# rtk1010_test.net
KiCad netlist of a schematic drawn in EAGLE
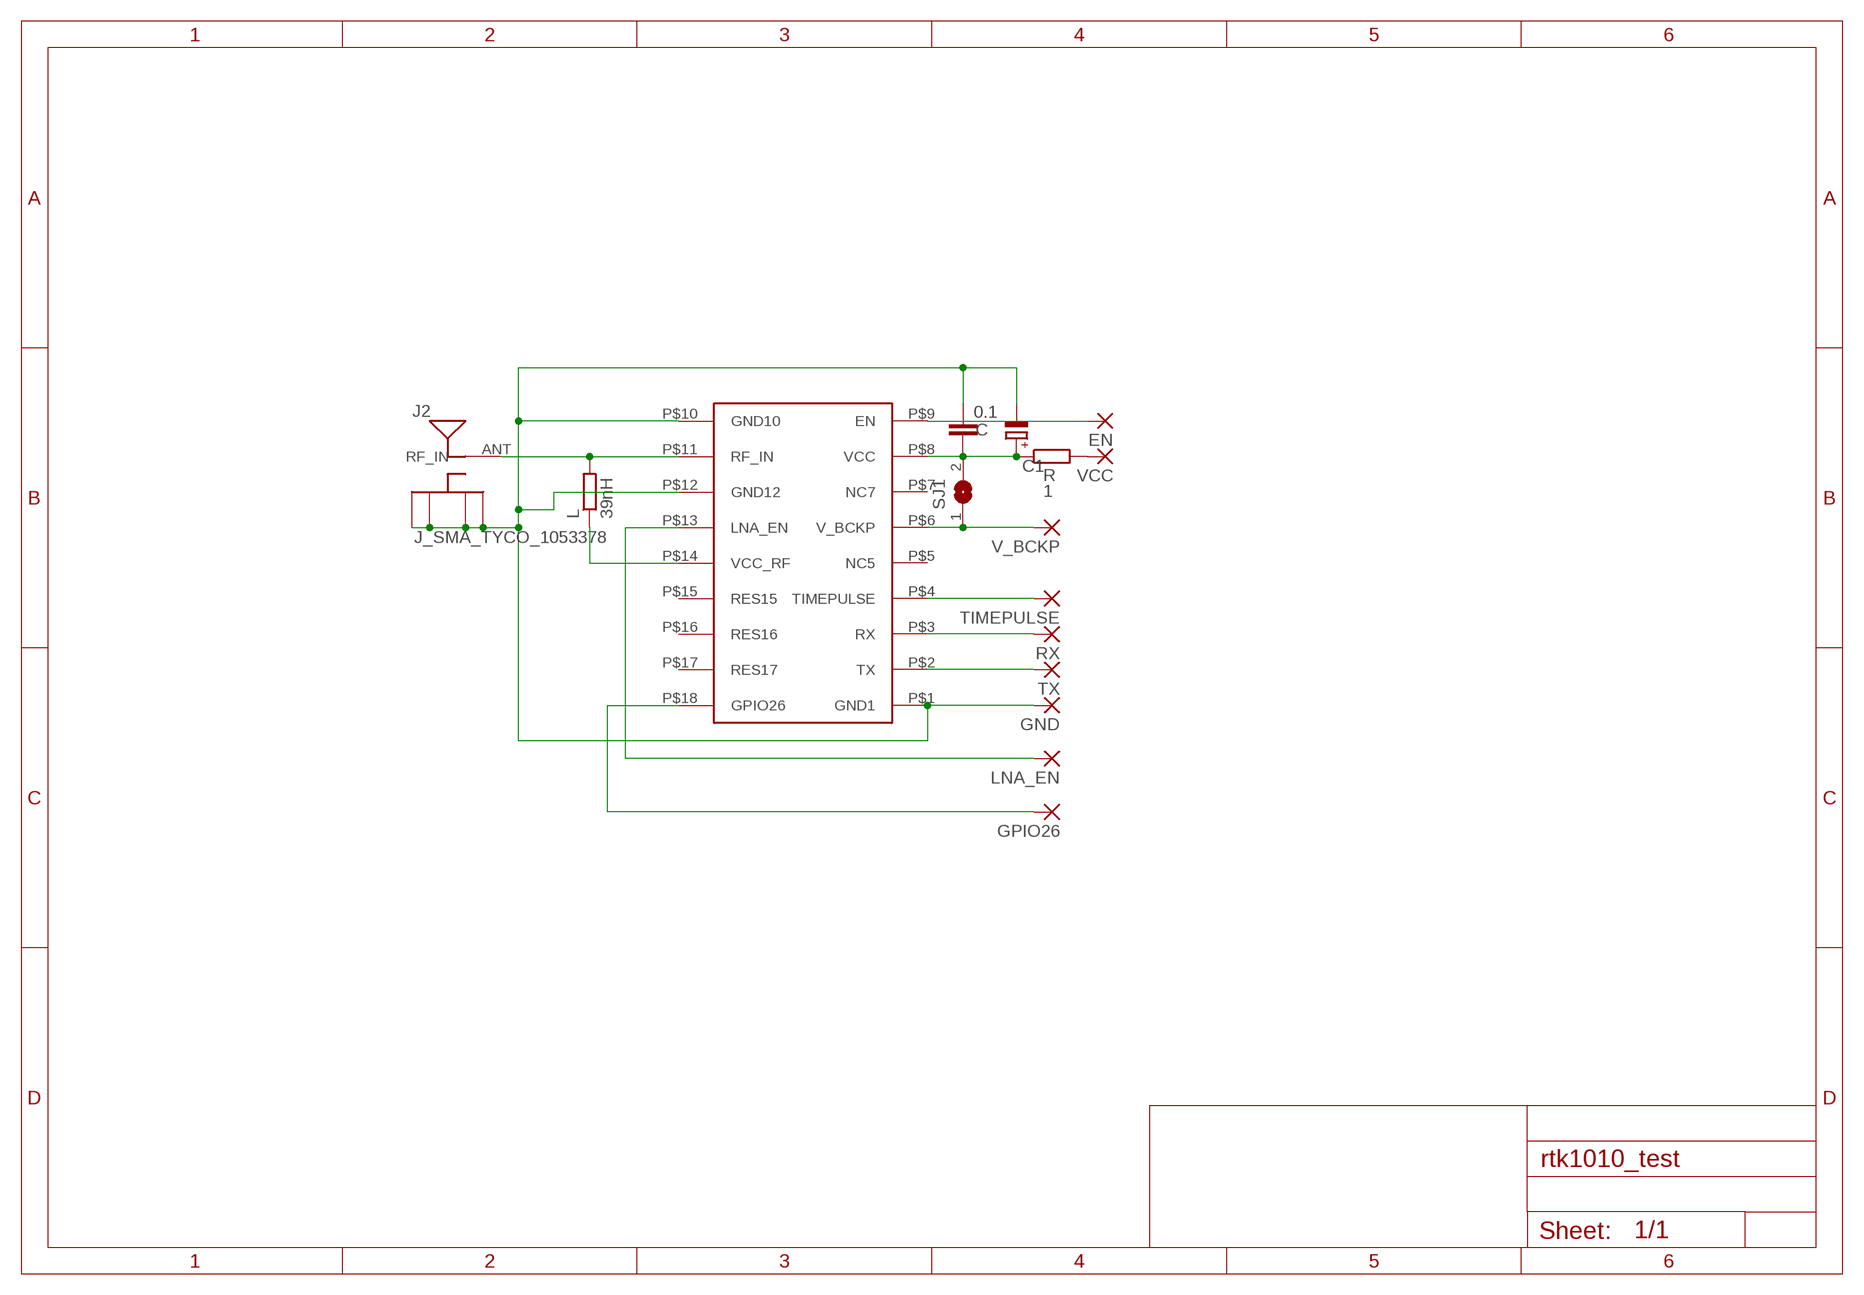
[diagram p0: schematic, sheet 1]

(export (version "E")
  (design (tool "Eeschema 10.0.6"))
  (components
    (comp (ref "C")
      (value "0.1")
      (footprint "eagle-import:C0805")
      (libsource (lib "eagle-import") (part "C-EUC0805"))
    )
    (comp (ref "C1")
      (value "CPOL-EUSMCB")
      (footprint "eagle-import:SMC_B")
      (libsource (lib "eagle-import") (part "CPOL-EUSMCB"))
    )
    (comp (ref "EN")
      (value "2,15/1,0")
      (footprint "eagle-import:2,15_1,0")
      (libsource (lib "eagle-import") (part "2,15/1,0"))
    )
    (comp (ref "GND")
      (value "2,15/1,0")
      (footprint "eagle-import:2,15_1,0")
      (libsource (lib "eagle-import") (part "2,15/1,0"))
    )
    (comp (ref "GPIO26")
      (value "2,15/1,0")
      (footprint "eagle-import:2,15_1,0")
      (libsource (lib "eagle-import") (part "2,15/1,0"))
    )
    (comp (ref "J2")
      (value "J_SMA_TYCO_1053378")
      (footprint "eagle-import:1053378-1")
      (libsource (lib "eagle-import") (part "J_SMA_TYCO_1053378"))
    )
    (comp (ref "L")
      (value "39nH")
      (footprint "eagle-import:R0805")
      (libsource (lib "eagle-import") (part "R-EU_R0805"))
    )
    (comp (ref "LNA_EN")
      (value "2,15/1,0")
      (footprint "eagle-import:2,15_1,0")
      (libsource (lib "eagle-import") (part "2,15/1,0"))
    )
    (comp (ref "R")
      (value "1")
      (footprint "eagle-import:R0805")
      (libsource (lib "eagle-import") (part "R-EU_R0805"))
    )
    (comp (ref "RX")
      (value "2,15/1,0")
      (footprint "eagle-import:2,15_1,0")
      (libsource (lib "eagle-import") (part "2,15/1,0"))
    )
    (comp (ref "SJ1")
      (value "SJW")
      (footprint "eagle-import:SJW")
      (libsource (lib "eagle-import") (part "SJW"))
    )
    (comp (ref "TIMEPULSE")
      (value "2,15/1,0")
      (footprint "eagle-import:2,15_1,0")
      (libsource (lib "eagle-import") (part "2,15/1,0"))
    )
    (comp (ref "TX")
      (value "2,15/1,0")
      (footprint "eagle-import:2,15_1,0")
      (libsource (lib "eagle-import") (part "2,15/1,0"))
    )
    (comp (ref "U$1")
      (value "RTK-1010")
      (footprint "eagle-import:RTK-1010")
      (libsource (lib "eagle-import") (part "RTK-1010"))
    )
    (comp (ref "VCC")
      (value "2,15/1,0")
      (footprint "eagle-import:2,15_1,0")
      (libsource (lib "eagle-import") (part "2,15/1,0"))
    )
    (comp (ref "V_BCKP")
      (value "2,15/1,0")
      (footprint "eagle-import:2,15_1,0")
      (libsource (lib "eagle-import") (part "2,15/1,0"))
    )
  )
  (nets
    (net (code "1") (name "Net-(EN-P)") (class "Default")
      (node (ref "EN") (pin "1") (pinfunction "P_1") (pintype "passive"))
      (node (ref "U$1") (pin "P$9") (pinfunction "EN_P$9") (pintype "input"))
    )
    (net (code "2") (name "Net-(GND-P)") (class "Default")
      (node (ref "C") (pin "2") (pinfunction "2_2") (pintype "passive"))
      (node (ref "C1") (pin "-") (pinfunction "-_-") (pintype "passive"))
      (node (ref "GND") (pin "1") (pinfunction "P_1") (pintype "passive"))
      (node (ref "J2") (pin "GND_1") (pinfunction "RFGND_1_GND_1") (pintype "power_in"))
      (node (ref "J2") (pin "GND_2") (pinfunction "RFGND_2_GND_2") (pintype "power_in"))
      (node (ref "J2") (pin "GND_3") (pinfunction "RFGND_3_GND_3") (pintype "power_in"))
      (node (ref "J2") (pin "GND_4") (pinfunction "RFGND_4_GND_4") (pintype "power_in"))
      (node (ref "U$1") (pin "P$1") (pinfunction "GND1_P$1") (pintype "power_in"))
      (node (ref "U$1") (pin "P$10") (pinfunction "GND10_P$10") (pintype "power_in"))
      (node (ref "U$1") (pin "P$12") (pinfunction "GND12_P$12") (pintype "power_in"))
    )
    (net (code "3") (name "Net-(GPIO26-P)") (class "Default")
      (node (ref "GPIO26") (pin "1") (pinfunction "P_1") (pintype "passive"))
      (node (ref "U$1") (pin "P$18") (pinfunction "GPIO26_P$18") (pintype "bidirectional"))
    )
    (net (code "4") (name "Net-(J2-RF_IN)") (class "Default")
      (node (ref "J2") (pin "ANT") (pinfunction "RF_IN_ANT") (pintype "input"))
      (node (ref "L") (pin "2") (pinfunction "2_2") (pintype "passive"))
      (node (ref "U$1") (pin "P$11") (pinfunction "RF_IN_P$11") (pintype "passive"))
    )
    (net (code "5") (name "Net-(LNA_EN-P)") (class "Default")
      (node (ref "LNA_EN") (pin "1") (pinfunction "P_1") (pintype "passive"))
      (node (ref "U$1") (pin "P$13") (pinfunction "LNA_EN_P$13") (pintype "input"))
    )
    (net (code "6") (name "Net-(RX-P)") (class "Default")
      (node (ref "RX") (pin "1") (pinfunction "P_1") (pintype "passive"))
      (node (ref "U$1") (pin "P$3") (pinfunction "RX_P$3") (pintype "input"))
    )
    (net (code "7") (name "Net-(TIMEPULSE-P)") (class "Default")
      (node (ref "TIMEPULSE") (pin "1") (pinfunction "P_1") (pintype "passive"))
      (node (ref "U$1") (pin "P$4") (pinfunction "TIMEPULSE_P$4") (pintype "output"))
    )
    (net (code "8") (name "Net-(TX-P)") (class "Default")
      (node (ref "TX") (pin "1") (pinfunction "P_1") (pintype "passive"))
      (node (ref "U$1") (pin "P$2") (pinfunction "TX_P$2") (pintype "output"))
    )
    (net (code "9") (name "Net-(U$1-VCC)") (class "Default")
      (node (ref "C") (pin "1") (pinfunction "1_1") (pintype "passive"))
      (node (ref "C1") (pin "+") (pinfunction "+_+") (pintype "passive"))
      (node (ref "R") (pin "1") (pinfunction "1_1") (pintype "passive"))
      (node (ref "SJ1") (pin "2") (pinfunction "2_2") (pintype "passive"))
      (node (ref "U$1") (pin "P$8") (pinfunction "VCC_P$8") (pintype "power_in"))
    )
    (net (code "10") (name "Net-(U$1-VCC_RF)") (class "Default")
      (node (ref "L") (pin "1") (pinfunction "1_1") (pintype "passive"))
      (node (ref "U$1") (pin "P$14") (pinfunction "VCC_RF_P$14") (pintype "power_in"))
    )
    (net (code "11") (name "Net-(U$1-V_BCKP)") (class "Default")
      (node (ref "SJ1") (pin "1") (pinfunction "1_1") (pintype "passive"))
      (node (ref "U$1") (pin "P$6") (pinfunction "V_BCKP_P$6") (pintype "power_in"))
      (node (ref "V_BCKP") (pin "1") (pinfunction "P_1") (pintype "passive"))
    )
    (net (code "12") (name "Net-(VCC-P)") (class "Default")
      (node (ref "R") (pin "2") (pinfunction "2_2") (pintype "passive"))
      (node (ref "VCC") (pin "1") (pinfunction "P_1") (pintype "passive"))
    )
    (net (code "13") (name "unconnected-(U$1-NC5-PadP$5)") (class "Default")
      (node (ref "U$1") (pin "P$5") (pinfunction "NC5_P$5") (pintype "no_connect"))
    )
    (net (code "14") (name "unconnected-(U$1-NC7-PadP$7)") (class "Default")
      (node (ref "U$1") (pin "P$7") (pinfunction "NC7_P$7") (pintype "no_connect"))
    )
    (net (code "15") (name "unconnected-(U$1-RES15-PadP$15)") (class "Default")
      (node (ref "U$1") (pin "P$15") (pinfunction "RES15_P$15") (pintype "no_connect"))
    )
    (net (code "16") (name "unconnected-(U$1-RES16-PadP$16)") (class "Default")
      (node (ref "U$1") (pin "P$16") (pinfunction "RES16_P$16") (pintype "no_connect"))
    )
    (net (code "17") (name "unconnected-(U$1-RES17-PadP$17)") (class "Default")
      (node (ref "U$1") (pin "P$17") (pinfunction "RES17_P$17") (pintype "no_connect"))
    )
  )
)
